# Irrig_schematic.net
KiCad netlist of a schematic drawn in EAGLE
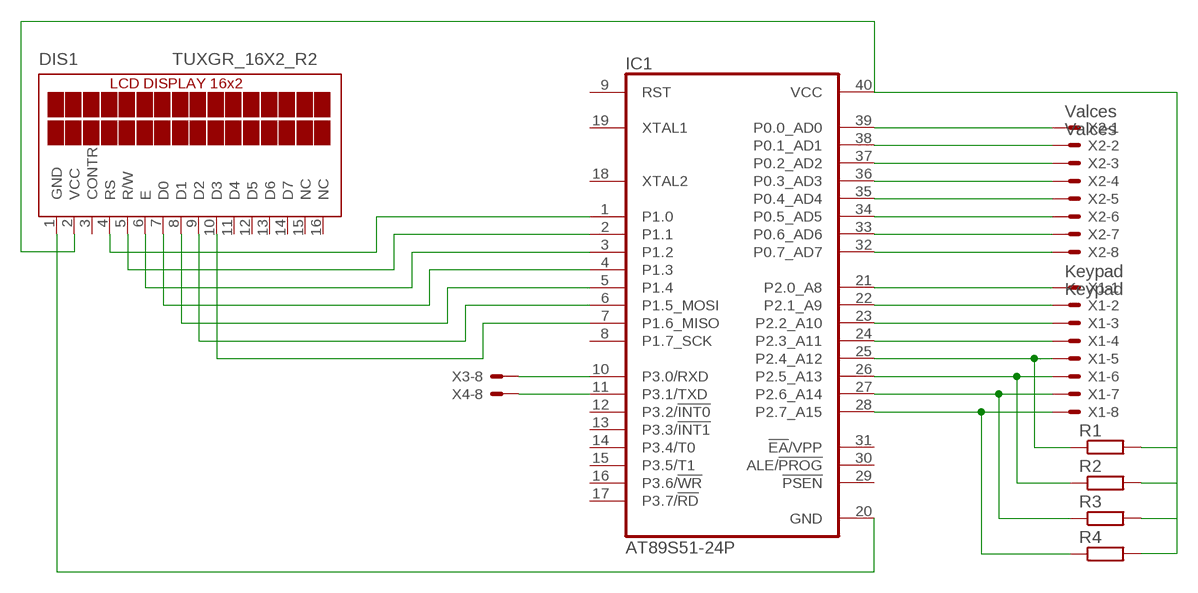
[diagram p0: schematic, sheet 1]

(export (version "E")
  (design (tool "Eeschema 10.0.6"))
  (components
    (comp (ref "DIS1")
      (value "TUXGR_16X2_R2")
      (footprint "eagle-import:TUXGR_16X2_R2")
      (libsource (lib "eagle-import") (part "TUXGR_16X2_R2"))
    )
    (comp (ref "IC1")
      (value "AT89S51-24P")
      (footprint "eagle-import:DIL40")
      (fields (field (name "MPN") "AT89S51-24PU"))
      (libsource (lib "eagle-import") (part "AT89S51-P24"))
    )
    (comp (ref "R1")
      (value "R-EU_0204/5")
      (footprint "eagle-import:0204_5")
      (libsource (lib "eagle-import") (part "R-EU_0204/5"))
    )
    (comp (ref "R2")
      (value "R-EU_0204/5")
      (footprint "eagle-import:0204_5")
      (libsource (lib "eagle-import") (part "R-EU_0204/5"))
    )
    (comp (ref "R3")
      (value "R-EU_0204/5")
      (footprint "eagle-import:0204_5")
      (libsource (lib "eagle-import") (part "R-EU_0204/5"))
    )
    (comp (ref "R4")
      (value "R-EU_0204/5")
      (footprint "eagle-import:0204_5")
      (libsource (lib "eagle-import") (part "R-EU_0204/5"))
    )
    (comp (ref "X1")
      (value "Keypad")
      (footprint "eagle-import:332-16")
      (libsource (lib "eagle-import") (part "332-16"))
    )
    (comp (ref "X2")
      (value "Valces")
      (footprint "eagle-import:332-16")
      (libsource (lib "eagle-import") (part "332-16"))
    )
    (comp (ref "X3")
      (value "Motor")
      (footprint "eagle-import:332-16")
      (libsource (lib "eagle-import") (part "332-16"))
    )
    (comp (ref "X4")
      (value "Motor")
      (footprint "eagle-import:332-16")
      (libsource (lib "eagle-import") (part "332-16"))
    )
  )
  (nets
    (net (code "1") (name "Net-(DIS1-D0)") (class "Default")
      (node (ref "DIS1") (pin "7") (pinfunction "D0_7") (pintype "input"))
      (node (ref "IC1") (pin "4") (pinfunction "P1.3_4") (pintype "bidirectional"))
    )
    (net (code "2") (name "Net-(DIS1-D1)") (class "Default")
      (node (ref "DIS1") (pin "8") (pinfunction "D1_8") (pintype "input"))
      (node (ref "IC1") (pin "5") (pinfunction "P1.4_5") (pintype "bidirectional"))
    )
    (net (code "3") (name "Net-(DIS1-D2)") (class "Default")
      (node (ref "DIS1") (pin "9") (pinfunction "D2_9") (pintype "input"))
      (node (ref "IC1") (pin "6") (pinfunction "P1.5_MOSI_6") (pintype "bidirectional"))
    )
    (net (code "4") (name "Net-(DIS1-D3)") (class "Default")
      (node (ref "DIS1") (pin "10") (pinfunction "D3_10") (pintype "input"))
      (node (ref "IC1") (pin "7") (pinfunction "P1.6_MISO_7") (pintype "bidirectional"))
    )
    (net (code "5") (name "Net-(DIS1-E)") (class "Default")
      (node (ref "DIS1") (pin "6") (pinfunction "E_6") (pintype "input"))
      (node (ref "IC1") (pin "3") (pinfunction "P1.2_3") (pintype "bidirectional"))
    )
    (net (code "6") (name "Net-(DIS1-GND)") (class "Default")
      (node (ref "DIS1") (pin "1") (pinfunction "GND_1") (pintype "power_in"))
      (node (ref "IC1") (pin "20") (pinfunction "GND_20") (pintype "power_in"))
    )
    (net (code "7") (name "Net-(DIS1-RS)") (class "Default")
      (node (ref "DIS1") (pin "4") (pinfunction "RS_4") (pintype "input"))
      (node (ref "IC1") (pin "1") (pinfunction "P1.0_1") (pintype "bidirectional"))
    )
    (net (code "8") (name "Net-(DIS1-R{slash}W)") (class "Default")
      (node (ref "DIS1") (pin "5") (pinfunction "R/W_5") (pintype "input"))
      (node (ref "IC1") (pin "2") (pinfunction "P1.1_2") (pintype "bidirectional"))
    )
    (net (code "9") (name "Net-(DIS1-VCC)") (class "Default")
      (node (ref "DIS1") (pin "2") (pinfunction "VCC_2") (pintype "power_in"))
      (node (ref "IC1") (pin "40") (pinfunction "VCC_40") (pintype "power_in"))
      (node (ref "R1") (pin "2") (pinfunction "2_2") (pintype "passive"))
      (node (ref "R2") (pin "2") (pinfunction "2_2") (pintype "passive"))
      (node (ref "R3") (pin "2") (pinfunction "2_2") (pintype "passive"))
      (node (ref "R4") (pin "2") (pinfunction "2_2") (pintype "passive"))
    )
    (net (code "10") (name "Net-(IC1-P0.0_AD0)") (class "Default")
      (node (ref "IC1") (pin "39") (pinfunction "P0.0_AD0_39") (pintype "bidirectional"))
      (node (ref "X2") (pin "1") (pinfunction "S_1") (pintype "passive"))
    )
    (net (code "11") (name "Net-(IC1-P0.1_AD1)") (class "Default")
      (node (ref "IC1") (pin "38") (pinfunction "P0.1_AD1_38") (pintype "bidirectional"))
      (node (ref "X2") (pin "2") (pinfunction "S_2") (pintype "passive"))
    )
    (net (code "12") (name "Net-(IC1-P0.2_AD2)") (class "Default")
      (node (ref "IC1") (pin "37") (pinfunction "P0.2_AD2_37") (pintype "bidirectional"))
      (node (ref "X2") (pin "3") (pinfunction "S_3") (pintype "passive"))
    )
    (net (code "13") (name "Net-(IC1-P0.3_AD3)") (class "Default")
      (node (ref "IC1") (pin "36") (pinfunction "P0.3_AD3_36") (pintype "bidirectional"))
      (node (ref "X2") (pin "4") (pinfunction "S_4") (pintype "passive"))
    )
    (net (code "14") (name "Net-(IC1-P0.4_AD4)") (class "Default")
      (node (ref "IC1") (pin "35") (pinfunction "P0.4_AD4_35") (pintype "bidirectional"))
      (node (ref "X2") (pin "5") (pinfunction "S_5") (pintype "passive"))
    )
    (net (code "15") (name "Net-(IC1-P0.5_AD5)") (class "Default")
      (node (ref "IC1") (pin "34") (pinfunction "P0.5_AD5_34") (pintype "bidirectional"))
      (node (ref "X2") (pin "6") (pinfunction "S_6") (pintype "passive"))
    )
    (net (code "16") (name "Net-(IC1-P0.6_AD6)") (class "Default")
      (node (ref "IC1") (pin "33") (pinfunction "P0.6_AD6_33") (pintype "bidirectional"))
      (node (ref "X2") (pin "7") (pinfunction "S_7") (pintype "passive"))
    )
    (net (code "17") (name "Net-(IC1-P0.7_AD7)") (class "Default")
      (node (ref "IC1") (pin "32") (pinfunction "P0.7_AD7_32") (pintype "bidirectional"))
      (node (ref "X2") (pin "8") (pinfunction "S_8") (pintype "passive"))
    )
    (net (code "18") (name "Net-(IC1-P2.0_A8)") (class "Default")
      (node (ref "IC1") (pin "21") (pinfunction "P2.0_A8_21") (pintype "bidirectional"))
      (node (ref "X1") (pin "1") (pinfunction "S_1") (pintype "passive"))
    )
    (net (code "19") (name "Net-(IC1-P2.1_A9)") (class "Default")
      (node (ref "IC1") (pin "22") (pinfunction "P2.1_A9_22") (pintype "bidirectional"))
      (node (ref "X1") (pin "2") (pinfunction "S_2") (pintype "passive"))
    )
    (net (code "20") (name "Net-(IC1-P2.2_A10)") (class "Default")
      (node (ref "IC1") (pin "23") (pinfunction "P2.2_A10_23") (pintype "bidirectional"))
      (node (ref "X1") (pin "3") (pinfunction "S_3") (pintype "passive"))
    )
    (net (code "21") (name "Net-(IC1-P2.3_A11)") (class "Default")
      (node (ref "IC1") (pin "24") (pinfunction "P2.3_A11_24") (pintype "bidirectional"))
      (node (ref "X1") (pin "4") (pinfunction "S_4") (pintype "passive"))
    )
    (net (code "22") (name "Net-(IC1-P2.4_A12)") (class "Default")
      (node (ref "IC1") (pin "25") (pinfunction "P2.4_A12_25") (pintype "bidirectional"))
      (node (ref "R1") (pin "1") (pinfunction "1_1") (pintype "passive"))
      (node (ref "X1") (pin "5") (pinfunction "S_5") (pintype "passive"))
    )
    (net (code "23") (name "Net-(IC1-P2.5_A13)") (class "Default")
      (node (ref "IC1") (pin "26") (pinfunction "P2.5_A13_26") (pintype "bidirectional"))
      (node (ref "R2") (pin "1") (pinfunction "1_1") (pintype "passive"))
      (node (ref "X1") (pin "6") (pinfunction "S_6") (pintype "passive"))
    )
    (net (code "24") (name "Net-(IC1-P2.6_A14)") (class "Default")
      (node (ref "IC1") (pin "27") (pinfunction "P2.6_A14_27") (pintype "bidirectional"))
      (node (ref "R3") (pin "1") (pinfunction "1_1") (pintype "passive"))
      (node (ref "X1") (pin "7") (pinfunction "S_7") (pintype "passive"))
    )
    (net (code "25") (name "Net-(IC1-P2.7_A15)") (class "Default")
      (node (ref "IC1") (pin "28") (pinfunction "P2.7_A15_28") (pintype "bidirectional"))
      (node (ref "R4") (pin "1") (pinfunction "1_1") (pintype "passive"))
      (node (ref "X1") (pin "8") (pinfunction "S_8") (pintype "passive"))
    )
    (net (code "26") (name "Net-(IC1-P3.0{slash}RXD)") (class "Default")
      (node (ref "IC1") (pin "10") (pinfunction "P3.0/RXD_10") (pintype "bidirectional"))
      (node (ref "X3") (pin "8") (pinfunction "S_8") (pintype "passive"))
    )
    (net (code "27") (name "Net-(IC1-P3.1{slash}TXD)") (class "Default")
      (node (ref "IC1") (pin "11") (pinfunction "P3.1/TXD_11") (pintype "bidirectional"))
      (node (ref "X4") (pin "8") (pinfunction "S_8") (pintype "passive"))
    )
    (net (code "28") (name "unconnected-(DIS1-CONTR-Pad3)") (class "Default")
      (node (ref "DIS1") (pin "3") (pinfunction "CONTR_3") (pintype "input"))
    )
    (net (code "29") (name "unconnected-(DIS1-D4-Pad11)") (class "Default")
      (node (ref "DIS1") (pin "11") (pinfunction "D4_11") (pintype "input"))
    )
    (net (code "30") (name "unconnected-(DIS1-D5-Pad12)") (class "Default")
      (node (ref "DIS1") (pin "12") (pinfunction "D5_12") (pintype "input"))
    )
    (net (code "31") (name "unconnected-(DIS1-D6-Pad13)") (class "Default")
      (node (ref "DIS1") (pin "13") (pinfunction "D6_13") (pintype "input"))
    )
    (net (code "32") (name "unconnected-(DIS1-D7-Pad14)") (class "Default")
      (node (ref "DIS1") (pin "14") (pinfunction "D7_14") (pintype "input"))
    )
    (net (code "33") (name "unconnected-(DIS1-NC-Pad15)") (class "Default")
      (node (ref "DIS1") (pin "15") (pinfunction "NC_15") (pintype "no_connect"))
    )
    (net (code "34") (name "unconnected-(DIS1-NC-Pad16)") (class "Default")
      (node (ref "DIS1") (pin "16") (pinfunction "NC_16") (pintype "no_connect"))
    )
    (net (code "35") (name "unconnected-(IC1-ALE{slash}~{PROG}-Pad30)") (class "Default")
      (node (ref "IC1") (pin "30") (pinfunction "ALE/~{PROG}_30") (pintype "output"))
    )
    (net (code "36") (name "unconnected-(IC1-P1.7_SCK-Pad8)") (class "Default")
      (node (ref "IC1") (pin "8") (pinfunction "P1.7_SCK_8") (pintype "bidirectional"))
    )
    (net (code "37") (name "unconnected-(IC1-P3.2{slash}~{INT0}-Pad12)") (class "Default")
      (node (ref "IC1") (pin "12") (pinfunction "P3.2/~{INT0}_12") (pintype "bidirectional"))
    )
    (net (code "38") (name "unconnected-(IC1-P3.3{slash}~{INT1}-Pad13)") (class "Default")
      (node (ref "IC1") (pin "13") (pinfunction "P3.3/~{INT1}_13") (pintype "bidirectional"))
    )
    (net (code "39") (name "unconnected-(IC1-P3.4{slash}T0-Pad14)") (class "Default")
      (node (ref "IC1") (pin "14") (pinfunction "P3.4/T0_14") (pintype "bidirectional"))
    )
    (net (code "40") (name "unconnected-(IC1-P3.5{slash}T1-Pad15)") (class "Default")
      (node (ref "IC1") (pin "15") (pinfunction "P3.5/T1_15") (pintype "bidirectional"))
    )
    (net (code "41") (name "unconnected-(IC1-P3.6{slash}~{WR}-Pad16)") (class "Default")
      (node (ref "IC1") (pin "16") (pinfunction "P3.6/~{WR}_16") (pintype "bidirectional"))
    )
    (net (code "42") (name "unconnected-(IC1-P3.7{slash}~{RD}-Pad17)") (class "Default")
      (node (ref "IC1") (pin "17") (pinfunction "P3.7/~{RD}_17") (pintype "bidirectional"))
    )
    (net (code "43") (name "unconnected-(IC1-RST-Pad9)") (class "Default")
      (node (ref "IC1") (pin "9") (pinfunction "RST_9") (pintype "input"))
    )
    (net (code "44") (name "unconnected-(IC1-XTAL1-Pad19)") (class "Default")
      (node (ref "IC1") (pin "19") (pinfunction "XTAL1_19") (pintype "input"))
    )
    (net (code "45") (name "unconnected-(IC1-XTAL2-Pad18)") (class "Default")
      (node (ref "IC1") (pin "18") (pinfunction "XTAL2_18") (pintype "input"))
    )
    (net (code "46") (name "unconnected-(IC1-~{EA}{slash}VPP-Pad31)") (class "Default")
      (node (ref "IC1") (pin "31") (pinfunction "~{EA}/VPP_31") (pintype "input"))
    )
    (net (code "47") (name "unconnected-(IC1-~{PSEN}-Pad29)") (class "Default")
      (node (ref "IC1") (pin "29") (pinfunction "~{PSEN}_29") (pintype "output"))
    )
  )
)
